# LedCtlV2.net
KiCad netlist of a schematic drawn in EAGLE
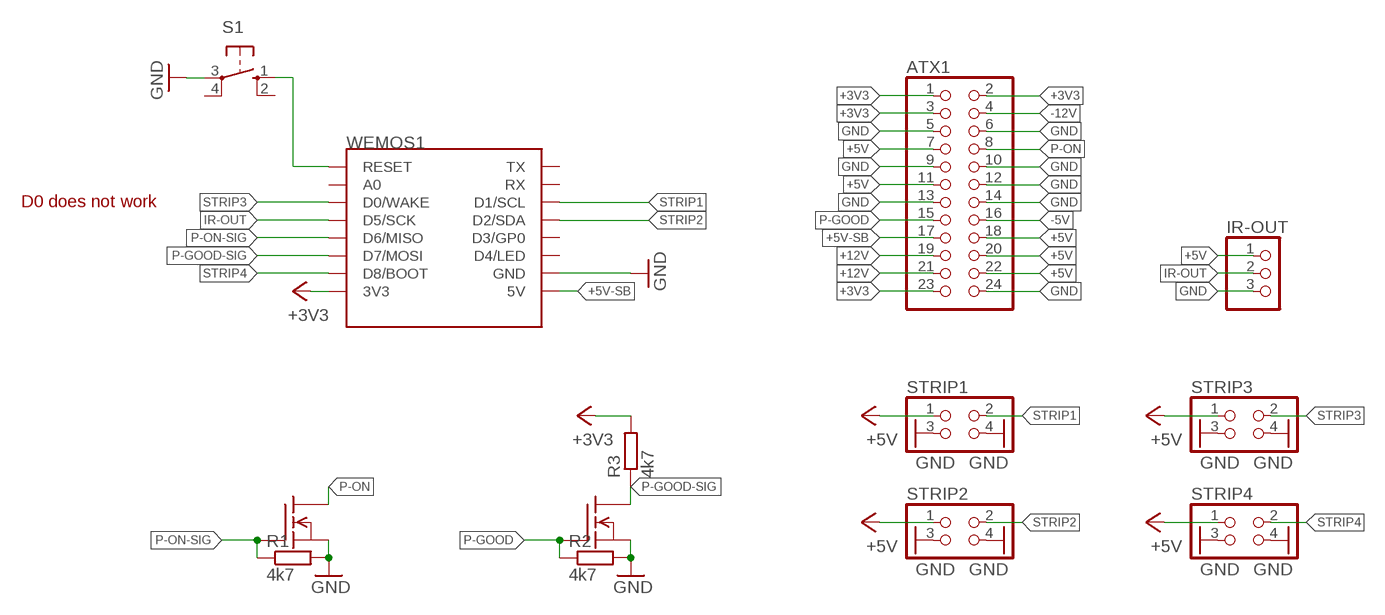
[diagram p0: schematic, sheet 1]

(export (version "E")
  (design (tool "Eeschema 10.0.6"))
  (components
    (comp (ref "ATX1")
      (value "PINHD-2X12_2.54")
      (footprint "eagle-import:2X12")
      (libsource (lib "eagle-import") (part "PINHD-2X12_2.54"))
    )
    (comp (ref "IR-OUT")
      (value "PINHD-1X03_2.54-S")
      (footprint "eagle-import:1X03-S")
      (libsource (lib "eagle-import") (part "PINHD-1X03_2.54-S"))
    )
    (comp (ref "Q1")
      (value "FQN1N50CI")
      (footprint "eagle-import:TO92-INLINE")
      (libsource (lib "eagle-import") (part "FQN1N50CI"))
    )
    (comp (ref "Q2")
      (value "FQN1N50CI")
      (footprint "eagle-import:TO92-INLINE")
      (libsource (lib "eagle-import") (part "FQN1N50CI"))
    )
    (comp (ref "R1")
      (value "4k7")
      (footprint "eagle-import:0207_10")
      (libsource (lib "eagle-import") (part "R-EU_0207/10"))
    )
    (comp (ref "R2")
      (value "4k7")
      (footprint "eagle-import:0207_10")
      (libsource (lib "eagle-import") (part "R-EU_0207/10"))
    )
    (comp (ref "R3")
      (value "4k7")
      (footprint "eagle-import:0207_10")
      (libsource (lib "eagle-import") (part "R-EU_0207/10"))
    )
    (comp (ref "S1")
      (value "10-XX")
      (footprint "eagle-import:B3F-10XX")
      (fields (field (name "MPN") "B3F-1000"))
      (libsource (lib "eagle-import") (part "10-XX"))
    )
    (comp (ref "STRIP1")
      (value "PINHD-2X02_2.54")
      (footprint "eagle-import:2X02")
      (libsource (lib "eagle-import") (part "PINHD-2X02_2.54"))
    )
    (comp (ref "STRIP2")
      (value "PINHD-2X02_2.54")
      (footprint "eagle-import:2X02")
      (libsource (lib "eagle-import") (part "PINHD-2X02_2.54"))
    )
    (comp (ref "STRIP3")
      (value "PINHD-2X02_2.54")
      (footprint "eagle-import:2X02")
      (libsource (lib "eagle-import") (part "PINHD-2X02_2.54"))
    )
    (comp (ref "STRIP4")
      (value "PINHD-2X02_2.54")
      (footprint "eagle-import:2X02")
      (libsource (lib "eagle-import") (part "PINHD-2X02_2.54"))
    )
    (comp (ref "WEMOS1")
      (value "WEMOS-D1-MINI")
      (footprint "eagle-import:WEMOS-D1-MINI")
      (libsource (lib "eagle-import") (part "WEMOS-D1-MINI"))
    )
  )
  (nets
    (net (code "1") (name "+3V3") (class "Default")
      (node (ref "ATX1") (pin "1") (pinfunction "1_1") (pintype "passive"))
      (node (ref "ATX1") (pin "2") (pinfunction "2_2") (pintype "passive"))
      (node (ref "ATX1") (pin "23") (pinfunction "23_23") (pintype "passive"))
      (node (ref "ATX1") (pin "3") (pinfunction "3_3") (pintype "passive"))
      (node (ref "R3") (pin "2") (pinfunction "2_2") (pintype "passive"))
      (node (ref "WEMOS1") (pin "3V3") (pinfunction "3V3_3V3") (pintype "bidirectional"))
    )
    (net (code "2") (name "+5V") (class "Default")
      (node (ref "ATX1") (pin "11") (pinfunction "11_11") (pintype "passive"))
      (node (ref "ATX1") (pin "18") (pinfunction "18_18") (pintype "passive"))
      (node (ref "ATX1") (pin "20") (pinfunction "20_20") (pintype "passive"))
      (node (ref "ATX1") (pin "22") (pinfunction "22_22") (pintype "passive"))
      (node (ref "ATX1") (pin "7") (pinfunction "7_7") (pintype "passive"))
      (node (ref "IR-OUT") (pin "1") (pinfunction "1_1") (pintype "passive"))
      (node (ref "STRIP1") (pin "1") (pinfunction "1_1") (pintype "passive"))
      (node (ref "STRIP2") (pin "1") (pinfunction "1_1") (pintype "passive"))
      (node (ref "STRIP3") (pin "1") (pinfunction "1_1") (pintype "passive"))
      (node (ref "STRIP4") (pin "1") (pinfunction "1_1") (pintype "passive"))
    )
    (net (code "3") (name "+5V-SB") (class "Default")
      (node (ref "ATX1") (pin "17") (pinfunction "17_17") (pintype "passive"))
      (node (ref "WEMOS1") (pin "5V") (pinfunction "5V_5V") (pintype "bidirectional"))
    )
    (net (code "4") (name "+12V") (class "Default")
      (node (ref "ATX1") (pin "19") (pinfunction "19_19") (pintype "passive"))
      (node (ref "ATX1") (pin "21") (pinfunction "21_21") (pintype "passive"))
    )
    (net (code "5") (name "-5V") (class "Default")
      (node (ref "ATX1") (pin "16") (pinfunction "16_16") (pintype "passive"))
    )
    (net (code "6") (name "-12V") (class "Default")
      (node (ref "ATX1") (pin "4") (pinfunction "4_4") (pintype "passive"))
    )
    (net (code "7") (name "GND") (class "Default")
      (node (ref "ATX1") (pin "10") (pinfunction "10_10") (pintype "passive"))
      (node (ref "ATX1") (pin "12") (pinfunction "12_12") (pintype "passive"))
      (node (ref "ATX1") (pin "13") (pinfunction "13_13") (pintype "passive"))
      (node (ref "ATX1") (pin "14") (pinfunction "14_14") (pintype "passive"))
      (node (ref "ATX1") (pin "24") (pinfunction "24_24") (pintype "passive"))
      (node (ref "ATX1") (pin "5") (pinfunction "5_5") (pintype "passive"))
      (node (ref "ATX1") (pin "6") (pinfunction "6_6") (pintype "passive"))
      (node (ref "ATX1") (pin "9") (pinfunction "9_9") (pintype "passive"))
      (node (ref "IR-OUT") (pin "3") (pinfunction "3_3") (pintype "passive"))
      (node (ref "Q1") (pin "3") (pinfunction "S_3") (pintype "passive"))
      (node (ref "Q2") (pin "3") (pinfunction "S_3") (pintype "passive"))
      (node (ref "R1") (pin "2") (pinfunction "2_2") (pintype "passive"))
      (node (ref "R2") (pin "2") (pinfunction "2_2") (pintype "passive"))
      (node (ref "S1") (pin "3") (pinfunction "P_3") (pintype "passive"))
      (node (ref "STRIP1") (pin "3") (pinfunction "3_3") (pintype "passive"))
      (node (ref "STRIP1") (pin "4") (pinfunction "4_4") (pintype "passive"))
      (node (ref "STRIP2") (pin "3") (pinfunction "3_3") (pintype "passive"))
      (node (ref "STRIP2") (pin "4") (pinfunction "4_4") (pintype "passive"))
      (node (ref "STRIP3") (pin "3") (pinfunction "3_3") (pintype "passive"))
      (node (ref "STRIP3") (pin "4") (pinfunction "4_4") (pintype "passive"))
      (node (ref "STRIP4") (pin "3") (pinfunction "3_3") (pintype "passive"))
      (node (ref "STRIP4") (pin "4") (pinfunction "4_4") (pintype "passive"))
      (node (ref "WEMOS1") (pin "GND") (pinfunction "GND_GND") (pintype "bidirectional"))
    )
    (net (code "8") (name "IR-OUT") (class "Default")
      (node (ref "IR-OUT") (pin "2") (pinfunction "2_2") (pintype "passive"))
      (node (ref "WEMOS1") (pin "D5") (pinfunction "D5/SCK_D5") (pintype "bidirectional"))
    )
    (net (code "9") (name "Net-(S1-S)") (class "Default")
      (node (ref "S1") (pin "1") (pinfunction "S_1") (pintype "passive"))
      (node (ref "WEMOS1") (pin "RESET") (pinfunction "RESET_RESET") (pintype "bidirectional"))
    )
    (net (code "10") (name "P-GOOD") (class "Default")
      (node (ref "ATX1") (pin "15") (pinfunction "15_15") (pintype "passive"))
      (node (ref "Q2") (pin "2") (pinfunction "G_2") (pintype "passive"))
      (node (ref "R2") (pin "1") (pinfunction "1_1") (pintype "passive"))
    )
    (net (code "11") (name "P-GOOD-SIG") (class "Default")
      (node (ref "Q2") (pin "1") (pinfunction "D_1") (pintype "passive"))
      (node (ref "R3") (pin "1") (pinfunction "1_1") (pintype "passive"))
      (node (ref "WEMOS1") (pin "D7") (pinfunction "D7/MOSI_D7") (pintype "bidirectional"))
    )
    (net (code "12") (name "P-ON") (class "Default")
      (node (ref "ATX1") (pin "8") (pinfunction "8_8") (pintype "passive"))
      (node (ref "Q1") (pin "1") (pinfunction "D_1") (pintype "passive"))
    )
    (net (code "13") (name "P-ON-SIG") (class "Default")
      (node (ref "Q1") (pin "2") (pinfunction "G_2") (pintype "passive"))
      (node (ref "R1") (pin "1") (pinfunction "1_1") (pintype "passive"))
      (node (ref "WEMOS1") (pin "D6") (pinfunction "D6/MISO_D6") (pintype "bidirectional"))
    )
    (net (code "14") (name "STRIP1") (class "Default")
      (node (ref "STRIP1") (pin "2") (pinfunction "2_2") (pintype "passive"))
      (node (ref "WEMOS1") (pin "D1") (pinfunction "D1/SCL_D1") (pintype "bidirectional"))
    )
    (net (code "15") (name "STRIP2") (class "Default")
      (node (ref "STRIP2") (pin "2") (pinfunction "2_2") (pintype "passive"))
      (node (ref "WEMOS1") (pin "D2") (pinfunction "D2/SDA_D2") (pintype "bidirectional"))
    )
    (net (code "16") (name "STRIP3") (class "Default")
      (node (ref "STRIP3") (pin "2") (pinfunction "2_2") (pintype "passive"))
      (node (ref "WEMOS1") (pin "D0") (pinfunction "D0/WAKE_D0") (pintype "bidirectional"))
    )
    (net (code "17") (name "STRIP4") (class "Default")
      (node (ref "STRIP4") (pin "2") (pinfunction "2_2") (pintype "passive"))
      (node (ref "WEMOS1") (pin "D8") (pinfunction "D8/BOOT_D8") (pintype "bidirectional"))
    )
    (net (code "18") (name "unconnected-(S1-P1-Pad4)") (class "Default")
      (node (ref "S1") (pin "4") (pinfunction "P1_4") (pintype "passive"))
    )
    (net (code "19") (name "unconnected-(S1-S1-Pad2)") (class "Default")
      (node (ref "S1") (pin "2") (pinfunction "S1_2") (pintype "passive"))
    )
    (net (code "20") (name "unconnected-(WEMOS1-D3{slash}GP0-PadD3)") (class "Default")
      (node (ref "WEMOS1") (pin "D3") (pinfunction "D3/GP0_D3") (pintype "bidirectional"))
    )
    (net (code "21") (name "unconnected-(WEMOS1-D4{slash}LED-PadD4)") (class "Default")
      (node (ref "WEMOS1") (pin "D4") (pinfunction "D4/LED_D4") (pintype "bidirectional"))
    )
    (net (code "22") (name "unconnected-(WEMOS1-PadA0)") (class "Default")
      (node (ref "WEMOS1") (pin "A0") (pinfunction "A0_A0") (pintype "bidirectional"))
    )
    (net (code "23") (name "unconnected-(WEMOS1-PadRX)") (class "Default")
      (node (ref "WEMOS1") (pin "RX") (pinfunction "RX_RX") (pintype "bidirectional"))
    )
    (net (code "24") (name "unconnected-(WEMOS1-PadTX)") (class "Default")
      (node (ref "WEMOS1") (pin "TX") (pinfunction "TX_TX") (pintype "bidirectional"))
    )
  )
)
